# hypnagogo.net
KiCad netlist of a schematic drawn in EAGLE
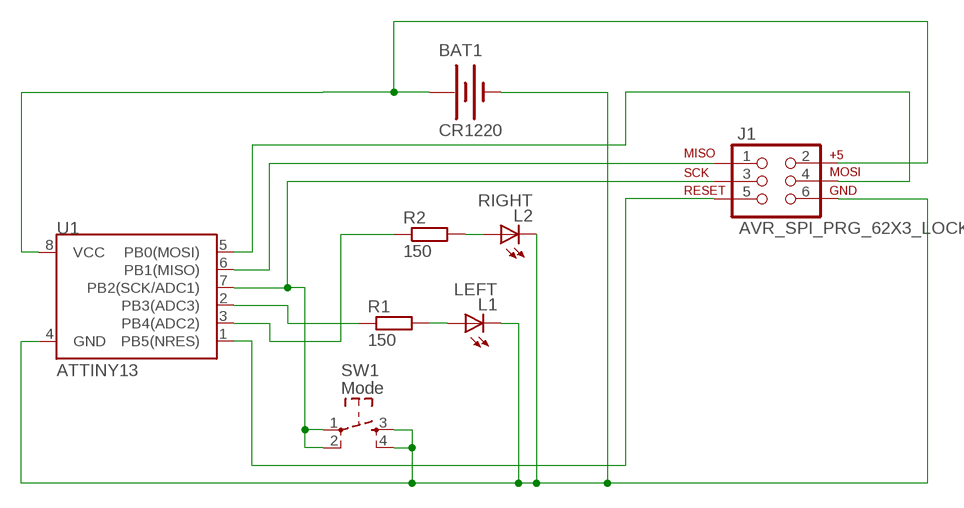
[diagram p0: schematic, sheet 1]

(export (version "E")
  (design (tool "Eeschema 10.0.6"))
  (components
    (comp (ref "BAT1")
      (value "CR1220")
      (footprint "eagle-import:BATTCON_12MM")
      (libsource (lib "eagle-import") (part "BATTERY12MM"))
    )
    (comp (ref "J1")
      (value "AVR_SPI_PRG_62X3_LOCK")
      (footprint "eagle-import:2X3_LOCK")
      (libsource (lib "eagle-import") (part "AVR_SPI_PRG_62X3_LOCK"))
    )
    (comp (ref "L1")
      (value "LEFT")
      (footprint "eagle-import:LED-3MM")
      (libsource (lib "eagle-import") (part "LED-3MM"))
    )
    (comp (ref "L2")
      (value "RIGHT")
      (footprint "eagle-import:LED-3MM")
      (libsource (lib "eagle-import") (part "LED-3MM"))
    )
    (comp (ref "R1")
      (value "150")
      (footprint "eagle-import:R805")
      (libsource (lib "eagle-import") (part "RESISTOR-0805R805"))
    )
    (comp (ref "R2")
      (value "150")
      (footprint "eagle-import:R805")
      (libsource (lib "eagle-import") (part "RESISTOR-0805R805"))
    )
    (comp (ref "SW1")
      (value "Mode")
      (footprint "eagle-import:SW_TACT_SMALL")
      (libsource (lib "eagle-import") (part "SW_TACT"))
    )
    (comp (ref "U1")
      (value "ATTINY13")
      (footprint "eagle-import:SO08")
      (libsource (lib "eagle-import") (part "ATTINY13SOIC"))
    )
  )
  (nets
    (net (code "1") (name "Net-(BAT1-+)") (class "Default")
      (node (ref "BAT1") (pin "PWR@1") (pinfunction "+_PWR@1") (pintype "power_in"))
      (node (ref "J1") (pin "2") (pinfunction "2_2") (pintype "passive"))
      (node (ref "U1") (pin "8") (pinfunction "VCC_8") (pintype "bidirectional"))
    )
    (net (code "2") (name "Net-(BAT1--)") (class "Default")
      (node (ref "BAT1") (pin "GND") (pinfunction "-_GND") (pintype "power_in"))
      (node (ref "J1") (pin "6") (pinfunction "6_6") (pintype "passive"))
      (node (ref "L1") (pin "K") (pinfunction "C_K") (pintype "passive"))
      (node (ref "L2") (pin "K") (pinfunction "C_K") (pintype "passive"))
      (node (ref "SW1") (pin "3") (pinfunction "3_3") (pintype "passive"))
      (node (ref "SW1") (pin "4") (pinfunction "4_4") (pintype "passive"))
      (node (ref "U1") (pin "4") (pinfunction "GND_4") (pintype "bidirectional"))
    )
    (net (code "3") (name "Net-(L1-PadA)") (class "Default")
      (node (ref "L1") (pin "A") (pinfunction "A_A") (pintype "passive"))
      (node (ref "R1") (pin "2") (pinfunction "2_2") (pintype "passive"))
    )
    (net (code "4") (name "Net-(L2-PadA)") (class "Default")
      (node (ref "L2") (pin "A") (pinfunction "A_A") (pintype "passive"))
      (node (ref "R2") (pin "2") (pinfunction "2_2") (pintype "passive"))
    )
    (net (code "5") (name "Net-(U1-PB0(MOSI))") (class "Default")
      (node (ref "J1") (pin "4") (pinfunction "4_4") (pintype "passive"))
      (node (ref "U1") (pin "5") (pinfunction "PB0(MOSI)_5") (pintype "bidirectional"))
    )
    (net (code "6") (name "Net-(U1-PB1(MISO))") (class "Default")
      (node (ref "J1") (pin "1") (pinfunction "1_1") (pintype "passive"))
      (node (ref "U1") (pin "6") (pinfunction "PB1(MISO)_6") (pintype "bidirectional"))
    )
    (net (code "7") (name "Net-(U1-PB2(SCK{slash}ADC1))") (class "Default")
      (node (ref "J1") (pin "3") (pinfunction "3_3") (pintype "passive"))
      (node (ref "SW1") (pin "1") (pinfunction "1_1") (pintype "passive"))
      (node (ref "SW1") (pin "2") (pinfunction "2_2") (pintype "passive"))
      (node (ref "U1") (pin "7") (pinfunction "PB2(SCK/ADC1)_7") (pintype "bidirectional"))
    )
    (net (code "8") (name "Net-(U1-PB3(ADC3))") (class "Default")
      (node (ref "R1") (pin "1") (pinfunction "1_1") (pintype "passive"))
      (node (ref "U1") (pin "2") (pinfunction "PB3(ADC3)_2") (pintype "bidirectional"))
    )
    (net (code "9") (name "Net-(U1-PB4(ADC2))") (class "Default")
      (node (ref "R2") (pin "1") (pinfunction "1_1") (pintype "passive"))
      (node (ref "U1") (pin "3") (pinfunction "PB4(ADC2)_3") (pintype "bidirectional"))
    )
    (net (code "10") (name "Net-(U1-PB5(NRES))") (class "Default")
      (node (ref "J1") (pin "5") (pinfunction "5_5") (pintype "passive"))
      (node (ref "U1") (pin "1") (pinfunction "PB5(NRES)_1") (pintype "bidirectional"))
    )
  )
)
